# DI_DO.net
KiCad netlist of a schematic drawn in Altium Designer
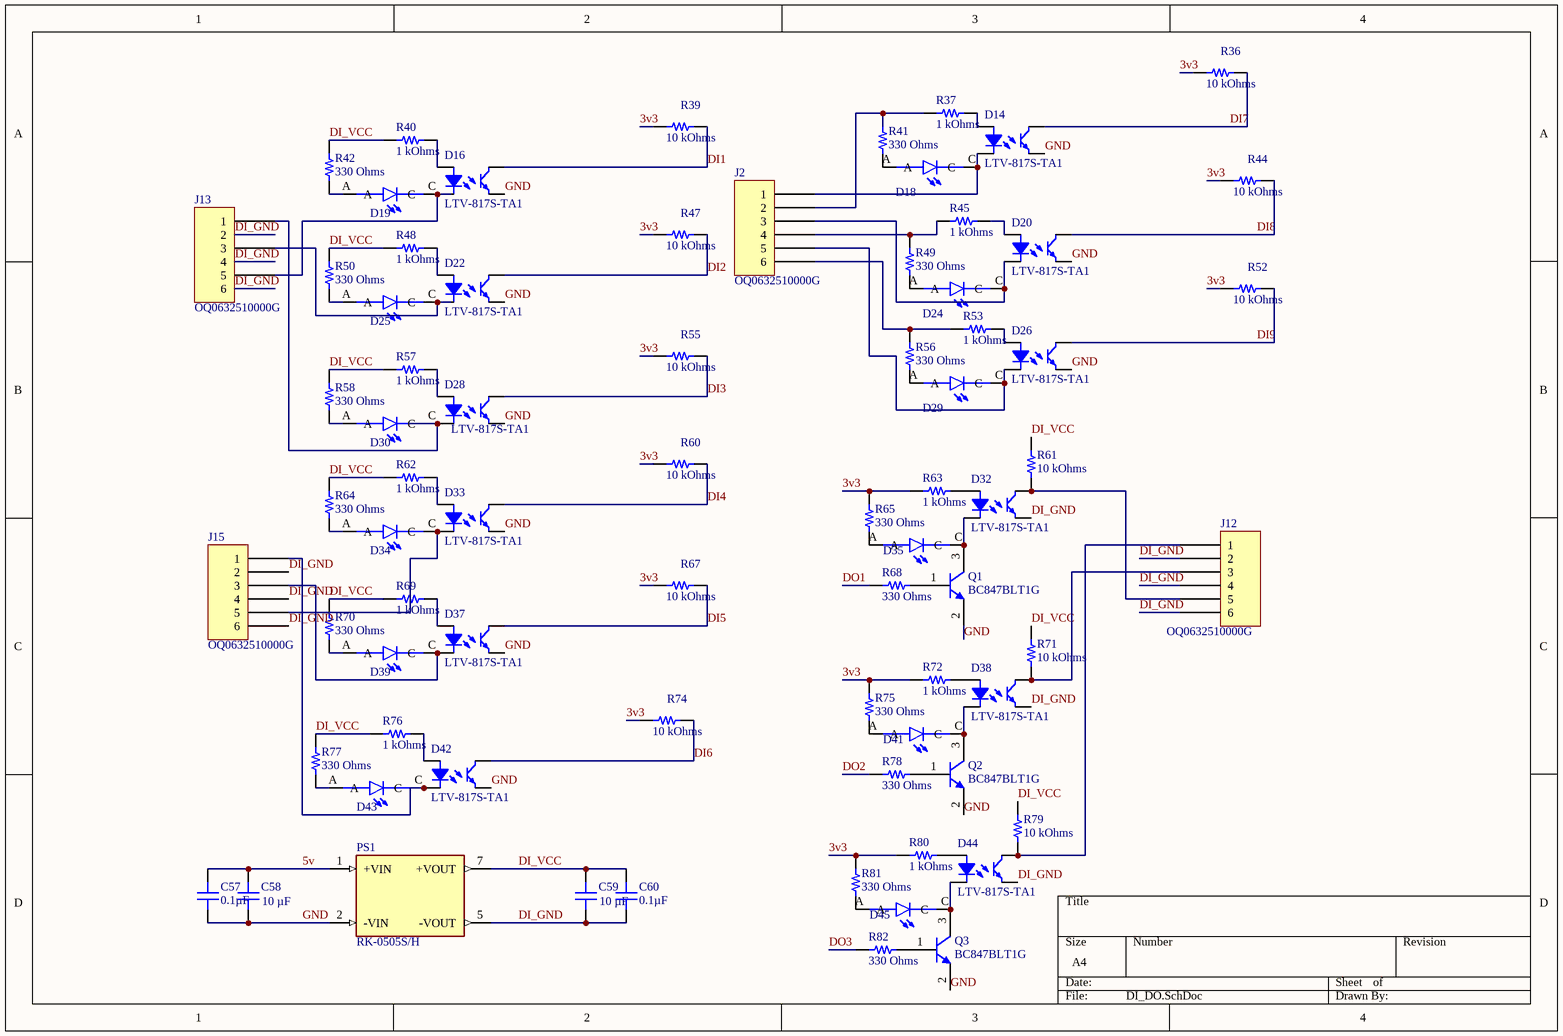
[diagram p0: DI_DO.SchDoc]

(export (version "E")
  (design (tool "Eeschema 10.0.6"))
  (components
    (comp (ref "C57")
      (value "1µF")
      (footprint "CAP 0805_2012")
      (description "CAP CER 1UF 10V X7R 0805")
      (fields
        (field (name "PART NUMBER") "0805ZC105KAT4A")
        (field (name "CAPACITANCE") "0.1µF")
        (field (name "MANUFACTURER") "AVX Corporation")
      )
      (libsource (lib "Celestial Altium Library - altium_library") (part "Capacitor"))
    )
    (comp (ref "C58")
      (value "10 µF")
      (footprint "CAP 1206_3216 - 0.8MM")
      (description "CAP CER 10UF 16V X5R 1206")
      (fields
        (field (name "PART NUMBER") "EMK316BJ106MD-T")
        (field (name "CAPACITANCE") "10 µF")
        (field (name "MANUFACTURER") "Taiyo Yuden")
      )
      (libsource (lib "Celestial Altium Library - altium_library") (part "Capacitor"))
    )
    (comp (ref "C59")
      (value "10 µF")
      (footprint "CAP 1206_3216 - 0.8MM")
      (description "CAP CER 10UF 16V X5R 1206")
      (fields
        (field (name "PART NUMBER") "EMK316BJ106MD-T")
        (field (name "CAPACITANCE") "10 µF")
        (field (name "MANUFACTURER") "Taiyo Yuden")
      )
      (libsource (lib "Celestial Altium Library - altium_library") (part "Capacitor"))
    )
    (comp (ref "C60")
      (value "1µF")
      (footprint "CAP 0805_2012")
      (description "CAP CER 1UF 10V X7R 0805")
      (fields
        (field (name "PART NUMBER") "0805ZC105KAT4A")
        (field (name "CAPACITANCE") "0.1µF")
        (field (name "MANUFACTURER") "AVX Corporation")
      )
      (libsource (lib "Celestial Altium Library - altium_library") (part "Capacitor"))
    )
    (comp (ref "D14")
      (value "LTV-817S-TA1")
      (footprint "LITEON LTV-817")
      (description "OPTOISOLATR 5KV TRANSISTOR 4-SMD")
      (fields (field (name "MANUFACTURER") "Lite-On Inc."))
      (libsource (lib "Celestial Altium Library - altium_library") (part "Optoisolator"))
    )
    (comp (ref "D16")
      (value "LTV-817S-TA1")
      (footprint "LITEON LTV-817")
      (description "OPTOISOLATR 5KV TRANSISTOR 4-SMD")
      (fields (field (name "MANUFACTURER") "Lite-On Inc."))
      (libsource (lib "Celestial Altium Library - altium_library") (part "Optoisolator"))
    )
    (comp (ref "D18")
      (value "597-3305-607F")
      (footprint "LEDC2012X70N")
      (description "LED Uni-Color Green 4-Pin Chip 0805 T/R")
      (libsource (lib "597-3305-607F") (part "597-3305-607F"))
    )
    (comp (ref "D19")
      (value "597-3305-607F")
      (footprint "LEDC2012X70N")
      (description "LED Uni-Color Green 4-Pin Chip 0805 T/R")
      (libsource (lib "597-3305-607F") (part "597-3305-607F"))
    )
    (comp (ref "D20")
      (value "LTV-817S-TA1")
      (footprint "LITEON LTV-817")
      (description "OPTOISOLATR 5KV TRANSISTOR 4-SMD")
      (fields (field (name "MANUFACTURER") "Lite-On Inc."))
      (libsource (lib "Celestial Altium Library - altium_library") (part "Optoisolator"))
    )
    (comp (ref "D22")
      (value "LTV-817S-TA1")
      (footprint "LITEON LTV-817")
      (description "OPTOISOLATR 5KV TRANSISTOR 4-SMD")
      (fields (field (name "MANUFACTURER") "Lite-On Inc."))
      (libsource (lib "Celestial Altium Library - altium_library") (part "Optoisolator"))
    )
    (comp (ref "D24")
      (value "597-3305-607F")
      (footprint "LEDC2012X70N")
      (description "LED Uni-Color Green 4-Pin Chip 0805 T/R")
      (libsource (lib "597-3305-607F") (part "597-3305-607F"))
    )
    (comp (ref "D25")
      (value "597-3305-607F")
      (footprint "LEDC2012X70N")
      (description "LED Uni-Color Green 4-Pin Chip 0805 T/R")
      (libsource (lib "597-3305-607F") (part "597-3305-607F"))
    )
    (comp (ref "D26")
      (value "LTV-817S-TA1")
      (footprint "LITEON LTV-817")
      (description "OPTOISOLATR 5KV TRANSISTOR 4-SMD")
      (fields (field (name "MANUFACTURER") "Lite-On Inc."))
      (libsource (lib "Celestial Altium Library - altium_library") (part "Optoisolator"))
    )
    (comp (ref "D28")
      (value "LTV-817S-TA1")
      (footprint "LITEON LTV-817")
      (description "OPTOISOLATR 5KV TRANSISTOR 4-SMD")
      (fields (field (name "MANUFACTURER") "Lite-On Inc."))
      (libsource (lib "Celestial Altium Library - altium_library") (part "Optoisolator"))
    )
    (comp (ref "D29")
      (value "597-3305-607F")
      (footprint "LEDC2012X70N")
      (description "LED Uni-Color Green 4-Pin Chip 0805 T/R")
      (libsource (lib "597-3305-607F") (part "597-3305-607F"))
    )
    (comp (ref "D30")
      (value "597-3305-607F")
      (footprint "LEDC2012X70N")
      (description "LED Uni-Color Green 4-Pin Chip 0805 T/R")
      (libsource (lib "597-3305-607F") (part "597-3305-607F"))
    )
    (comp (ref "D32")
      (value "LTV-817S-TA1")
      (footprint "LITEON LTV-817")
      (description "OPTOISOLATR 5KV TRANSISTOR 4-SMD")
      (fields (field (name "MANUFACTURER") "Lite-On Inc."))
      (libsource (lib "Celestial Altium Library - altium_library") (part "Optoisolator"))
    )
    (comp (ref "D33")
      (value "LTV-817S-TA1")
      (footprint "LITEON LTV-817")
      (description "OPTOISOLATR 5KV TRANSISTOR 4-SMD")
      (fields (field (name "MANUFACTURER") "Lite-On Inc."))
      (libsource (lib "Celestial Altium Library - altium_library") (part "Optoisolator"))
    )
    (comp (ref "D34")
      (value "597-3305-607F")
      (footprint "LEDC2012X70N")
      (description "LED Uni-Color Green 4-Pin Chip 0805 T/R")
      (libsource (lib "597-3305-607F") (part "597-3305-607F"))
    )
    (comp (ref "D35")
      (value "597-3305-607F")
      (footprint "LEDC2012X70N")
      (description "LED Uni-Color Green 4-Pin Chip 0805 T/R")
      (libsource (lib "597-3305-607F") (part "597-3305-607F"))
    )
    (comp (ref "D37")
      (value "LTV-817S-TA1")
      (footprint "LITEON LTV-817")
      (description "OPTOISOLATR 5KV TRANSISTOR 4-SMD")
      (fields (field (name "MANUFACTURER") "Lite-On Inc."))
      (libsource (lib "Celestial Altium Library - altium_library") (part "Optoisolator"))
    )
    (comp (ref "D38")
      (value "LTV-817S-TA1")
      (footprint "LITEON LTV-817")
      (description "OPTOISOLATR 5KV TRANSISTOR 4-SMD")
      (fields (field (name "MANUFACTURER") "Lite-On Inc."))
      (libsource (lib "Celestial Altium Library - altium_library") (part "Optoisolator"))
    )
    (comp (ref "D39")
      (value "597-3305-607F")
      (footprint "LEDC2012X70N")
      (description "LED Uni-Color Green 4-Pin Chip 0805 T/R")
      (libsource (lib "597-3305-607F") (part "597-3305-607F"))
    )
    (comp (ref "D41")
      (value "597-3305-607F")
      (footprint "LEDC2012X70N")
      (description "LED Uni-Color Green 4-Pin Chip 0805 T/R")
      (libsource (lib "597-3305-607F") (part "597-3305-607F"))
    )
    (comp (ref "D42")
      (value "LTV-817S-TA1")
      (footprint "LITEON LTV-817")
      (description "OPTOISOLATR 5KV TRANSISTOR 4-SMD")
      (fields (field (name "MANUFACTURER") "Lite-On Inc."))
      (libsource (lib "Celestial Altium Library - altium_library") (part "Optoisolator"))
    )
    (comp (ref "D43")
      (value "597-3305-607F")
      (footprint "LEDC2012X70N")
      (description "LED Uni-Color Green 4-Pin Chip 0805 T/R")
      (libsource (lib "597-3305-607F") (part "597-3305-607F"))
    )
    (comp (ref "D44")
      (value "LTV-817S-TA1")
      (footprint "LITEON LTV-817")
      (description "OPTOISOLATR 5KV TRANSISTOR 4-SMD")
      (fields (field (name "MANUFACTURER") "Lite-On Inc."))
      (libsource (lib "Celestial Altium Library - altium_library") (part "Optoisolator"))
    )
    (comp (ref "D45")
      (value "597-3305-607F")
      (footprint "LEDC2012X70N")
      (description "LED Uni-Color Green 4-Pin Chip 0805 T/R")
      (libsource (lib "597-3305-607F") (part "597-3305-607F"))
    )
    (comp (ref "J2")
      (value "OQ0632510000G")
      (footprint "FCI 06-381-6PIN")
      (description "TERM BLOCK HDR 6POS 90DEG 3.81MM")
      (fields (field (name "MANUFACTURER") "Amphenol Anytek"))
      (libsource (lib "Celestial Altium Library - altium_library") (part "6 Pin"))
    )
    (comp (ref "J12")
      (value "OQ0632510000G")
      (footprint "FCI 06-381-6PIN")
      (description "TERM BLOCK HDR 6POS 90DEG 3.81MM")
      (fields (field (name "MANUFACTURER") "Amphenol Anytek"))
      (libsource (lib "") (part "6 Pin_1"))
    )
    (comp (ref "J13")
      (value "OQ0632510000G")
      (footprint "FCI 06-381-6PIN")
      (description "TERM BLOCK HDR 6POS 90DEG 3.81MM")
      (fields (field (name "MANUFACTURER") "Amphenol Anytek"))
      (libsource (lib "Celestial Altium Library - altium_library") (part "6 Pin"))
    )
    (comp (ref "J15")
      (value "OQ0632510000G")
      (footprint "FCI 06-381-6PIN")
      (description "TERM BLOCK HDR 6POS 90DEG 3.81MM")
      (fields (field (name "MANUFACTURER") "Amphenol Anytek"))
      (libsource (lib "Celestial Altium Library - altium_library") (part "6 Pin"))
    )
    (comp (ref "PS1")
      (value "RK-0505S/H")
      (footprint "CONV_RK-0505S/H")
      (description "DC/DC Converter, 1 Watt, SIP7, Single Output")
      (fields (field (name "MF") "{'manufacturer': u'Recom Power'}"))
      (libsource (lib "RK-0505S_H") (part "RK-0505S/H"))
    )
    (comp (ref "Q1")
      (value "BC847BLT1G")
      (footprint "ON SEMI SOT-23-3")
      (description "TRANS NPN 45V 0.1A SOT23")
      (fields (field (name "MANUFACTURER") "ON Semiconductor"))
      (libsource (lib "Celestial Altium Library - altium_library") (part "ON SEMI NPN SOT-23-3"))
    )
    (comp (ref "Q2")
      (value "BC847BLT1G")
      (footprint "ON SEMI SOT-23-3")
      (description "TRANS NPN 45V 0.1A SOT23")
      (fields (field (name "MANUFACTURER") "ON Semiconductor"))
      (libsource (lib "Celestial Altium Library - altium_library") (part "ON SEMI NPN SOT-23-3"))
    )
    (comp (ref "Q3")
      (value "BC847BLT1G")
      (footprint "ON SEMI SOT-23-3")
      (description "TRANS NPN 45V 0.1A SOT23")
      (fields (field (name "MANUFACTURER") "ON Semiconductor"))
      (libsource (lib "Celestial Altium Library - altium_library") (part "ON SEMI NPN SOT-23-3"))
    )
    (comp (ref "R36")
      (value "10 kOhms")
      (footprint "RES 0805_2012")
      (description "RES SMD 10K OHM 1% 0.4W 0805")
      (fields (field (name "PART NUMBER") "ESR10EZPF1002") (field (name "MANUFACTURER") "Rohm Semiconductor"))
      (libsource (lib "Celestial Altium Library - altium_library") (part "Resistor"))
    )
    (comp (ref "R37")
      (value "1 kOhms")
      (footprint "RES 0805_2012")
      (description "RES SMD 1K OHM 1% 0.4W 0805")
      (fields (field (name "PART NUMBER") "ESR10EZPF1001") (field (name "MANUFACTURER") "Rohm Semiconductor"))
      (libsource (lib "Celestial Altium Library - altium_library") (part "Resistor"))
    )
    (comp (ref "R39")
      (value "10 kOhms")
      (footprint "RES 0805_2012")
      (description "RES SMD 10K OHM 1% 0.4W 0805")
      (fields (field (name "PART NUMBER") "ESR10EZPF1002") (field (name "MANUFACTURER") "Rohm Semiconductor"))
      (libsource (lib "Celestial Altium Library - altium_library") (part "Resistor"))
    )
    (comp (ref "R40")
      (value "1 kOhms")
      (footprint "RES 0805_2012")
      (description "RES SMD 1K OHM 1% 0.4W 0805")
      (fields (field (name "PART NUMBER") "ESR10EZPF1001") (field (name "MANUFACTURER") "Rohm Semiconductor"))
      (libsource (lib "Celestial Altium Library - altium_library") (part "Resistor"))
    )
    (comp (ref "R41")
      (value "330 Ohms")
      (footprint "RES 0805_2012")
      (description "RES SMD 330 OHM 1% 1/2W 0805")
      (fields (field (name "PART NUMBER") "CRCW0805330RFKEAHP") (field (name "MANUFACTURER") "Vishay Dale"))
      (libsource (lib "Celestial Altium Library - altium_library") (part "Resistor"))
    )
    (comp (ref "R42")
      (value "330 Ohms")
      (footprint "RES 0805_2012")
      (description "RES SMD 330 OHM 1% 1/2W 0805")
      (fields (field (name "PART NUMBER") "CRCW0805330RFKEAHP") (field (name "MANUFACTURER") "Vishay Dale"))
      (libsource (lib "Celestial Altium Library - altium_library") (part "Resistor"))
    )
    (comp (ref "R44")
      (value "10 kOhms")
      (footprint "RES 0805_2012")
      (description "RES SMD 10K OHM 1% 0.4W 0805")
      (fields (field (name "PART NUMBER") "ESR10EZPF1002") (field (name "MANUFACTURER") "Rohm Semiconductor"))
      (libsource (lib "Celestial Altium Library - altium_library") (part "Resistor"))
    )
    (comp (ref "R45")
      (value "1 kOhms")
      (footprint "RES 0805_2012")
      (description "RES SMD 1K OHM 1% 0.4W 0805")
      (fields (field (name "PART NUMBER") "ESR10EZPF1001") (field (name "MANUFACTURER") "Rohm Semiconductor"))
      (libsource (lib "Celestial Altium Library - altium_library") (part "Resistor"))
    )
    (comp (ref "R47")
      (value "10 kOhms")
      (footprint "RES 0805_2012")
      (description "RES SMD 10K OHM 1% 0.4W 0805")
      (fields (field (name "PART NUMBER") "ESR10EZPF1002") (field (name "MANUFACTURER") "Rohm Semiconductor"))
      (libsource (lib "Celestial Altium Library - altium_library") (part "Resistor"))
    )
    (comp (ref "R48")
      (value "1 kOhms")
      (footprint "RES 0805_2012")
      (description "RES SMD 1K OHM 1% 0.4W 0805")
      (fields (field (name "PART NUMBER") "ESR10EZPF1001") (field (name "MANUFACTURER") "Rohm Semiconductor"))
      (libsource (lib "Celestial Altium Library - altium_library") (part "Resistor"))
    )
    (comp (ref "R49")
      (value "330 Ohms")
      (footprint "RES 0805_2012")
      (description "RES SMD 330 OHM 1% 1/2W 0805")
      (fields (field (name "PART NUMBER") "CRCW0805330RFKEAHP") (field (name "MANUFACTURER") "Vishay Dale"))
      (libsource (lib "Celestial Altium Library - altium_library") (part "Resistor"))
    )
    (comp (ref "R50")
      (value "330 Ohms")
      (footprint "RES 0805_2012")
      (description "RES SMD 330 OHM 1% 1/2W 0805")
      (fields (field (name "PART NUMBER") "CRCW0805330RFKEAHP") (field (name "MANUFACTURER") "Vishay Dale"))
      (libsource (lib "Celestial Altium Library - altium_library") (part "Resistor"))
    )
    (comp (ref "R52")
      (value "10 kOhms")
      (footprint "RES 0805_2012")
      (description "RES SMD 10K OHM 1% 0.4W 0805")
      (fields (field (name "PART NUMBER") "ESR10EZPF1002") (field (name "MANUFACTURER") "Rohm Semiconductor"))
      (libsource (lib "Celestial Altium Library - altium_library") (part "Resistor"))
    )
    (comp (ref "R53")
      (value "1 kOhms")
      (footprint "RES 0805_2012")
      (description "RES SMD 1K OHM 1% 0.4W 0805")
      (fields (field (name "PART NUMBER") "ESR10EZPF1001") (field (name "MANUFACTURER") "Rohm Semiconductor"))
      (libsource (lib "Celestial Altium Library - altium_library") (part "Resistor"))
    )
    (comp (ref "R55")
      (value "10 kOhms")
      (footprint "RES 0805_2012")
      (description "RES SMD 10K OHM 1% 0.4W 0805")
      (fields (field (name "PART NUMBER") "ESR10EZPF1002") (field (name "MANUFACTURER") "Rohm Semiconductor"))
      (libsource (lib "Celestial Altium Library - altium_library") (part "Resistor"))
    )
    (comp (ref "R56")
      (value "330 Ohms")
      (footprint "RES 0805_2012")
      (description "RES SMD 330 OHM 1% 1/2W 0805")
      (fields (field (name "PART NUMBER") "CRCW0805330RFKEAHP") (field (name "MANUFACTURER") "Vishay Dale"))
      (libsource (lib "Celestial Altium Library - altium_library") (part "Resistor"))
    )
    (comp (ref "R57")
      (value "1 kOhms")
      (footprint "RES 0805_2012")
      (description "RES SMD 1K OHM 1% 0.4W 0805")
      (fields (field (name "PART NUMBER") "ESR10EZPF1001") (field (name "MANUFACTURER") "Rohm Semiconductor"))
      (libsource (lib "Celestial Altium Library - altium_library") (part "Resistor"))
    )
    (comp (ref "R58")
      (value "330 Ohms")
      (footprint "RES 0805_2012")
      (description "RES SMD 330 OHM 1% 1/2W 0805")
      (fields (field (name "PART NUMBER") "CRCW0805330RFKEAHP") (field (name "MANUFACTURER") "Vishay Dale"))
      (libsource (lib "Celestial Altium Library - altium_library") (part "Resistor"))
    )
    (comp (ref "R60")
      (value "10 kOhms")
      (footprint "RES 0805_2012")
      (description "RES SMD 10K OHM 1% 0.4W 0805")
      (fields (field (name "PART NUMBER") "ESR10EZPF1002") (field (name "MANUFACTURER") "Rohm Semiconductor"))
      (libsource (lib "Celestial Altium Library - altium_library") (part "Resistor"))
    )
    (comp (ref "R61")
      (value "10 kOhms")
      (footprint "RES 0805_2012")
      (description "RES SMD 10K OHM 1% 0.4W 0805")
      (fields (field (name "PART NUMBER") "ESR10EZPF1002") (field (name "MANUFACTURER") "Rohm Semiconductor"))
      (libsource (lib "Celestial Altium Library - altium_library") (part "Resistor"))
    )
    (comp (ref "R62")
      (value "1 kOhms")
      (footprint "RES 0805_2012")
      (description "RES SMD 1K OHM 1% 0.4W 0805")
      (fields (field (name "PART NUMBER") "ESR10EZPF1001") (field (name "MANUFACTURER") "Rohm Semiconductor"))
      (libsource (lib "Celestial Altium Library - altium_library") (part "Resistor"))
    )
    (comp (ref "R63")
      (value "1 kOhms")
      (footprint "RES 0805_2012")
      (description "RES SMD 1K OHM 1% 0.4W 0805")
      (fields (field (name "PART NUMBER") "ESR10EZPF1001") (field (name "MANUFACTURER") "Rohm Semiconductor"))
      (libsource (lib "Celestial Altium Library - altium_library") (part "Resistor"))
    )
    (comp (ref "R64")
      (value "330 Ohms")
      (footprint "RES 0805_2012")
      (description "RES SMD 330 OHM 1% 1/2W 0805")
      (fields (field (name "PART NUMBER") "CRCW0805330RFKEAHP") (field (name "MANUFACTURER") "Vishay Dale"))
      (libsource (lib "Celestial Altium Library - altium_library") (part "Resistor"))
    )
    (comp (ref "R65")
      (value "330 Ohms")
      (footprint "RES 0805_2012")
      (description "RES SMD 330 OHM 1% 1/2W 0805")
      (fields (field (name "PART NUMBER") "CRCW0805330RFKEAHP") (field (name "MANUFACTURER") "Vishay Dale"))
      (libsource (lib "Celestial Altium Library - altium_library") (part "Resistor"))
    )
    (comp (ref "R67")
      (value "10 kOhms")
      (footprint "RES 0805_2012")
      (description "RES SMD 10K OHM 1% 0.4W 0805")
      (fields (field (name "PART NUMBER") "ESR10EZPF1002") (field (name "MANUFACTURER") "Rohm Semiconductor"))
      (libsource (lib "Celestial Altium Library - altium_library") (part "Resistor"))
    )
    (comp (ref "R68")
      (value "330 Ohms")
      (footprint "RES 0805_2012")
      (description "RES SMD 330 OHM 1% 1/2W 0805")
      (fields (field (name "PART NUMBER") "CRCW0805330RFKEAHP") (field (name "MANUFACTURER") "Vishay Dale"))
      (libsource (lib "Celestial Altium Library - altium_library") (part "Resistor"))
    )
    (comp (ref "R69")
      (value "1 kOhms")
      (footprint "RES 0805_2012")
      (description "RES SMD 1K OHM 1% 0.4W 0805")
      (fields (field (name "PART NUMBER") "ESR10EZPF1001") (field (name "MANUFACTURER") "Rohm Semiconductor"))
      (libsource (lib "Celestial Altium Library - altium_library") (part "Resistor"))
    )
    (comp (ref "R70")
      (value "330 Ohms")
      (footprint "RES 0805_2012")
      (description "RES SMD 330 OHM 1% 1/2W 0805")
      (fields (field (name "PART NUMBER") "CRCW0805330RFKEAHP") (field (name "MANUFACTURER") "Vishay Dale"))
      (libsource (lib "Celestial Altium Library - altium_library") (part "Resistor"))
    )
    (comp (ref "R71")
      (value "10 kOhms")
      (footprint "RES 0805_2012")
      (description "RES SMD 10K OHM 1% 0.4W 0805")
      (fields (field (name "PART NUMBER") "ESR10EZPF1002") (field (name "MANUFACTURER") "Rohm Semiconductor"))
      (libsource (lib "Celestial Altium Library - altium_library") (part "Resistor"))
    )
    (comp (ref "R72")
      (value "1 kOhms")
      (footprint "RES 0805_2012")
      (description "RES SMD 1K OHM 1% 0.4W 0805")
      (fields (field (name "PART NUMBER") "ESR10EZPF1001") (field (name "MANUFACTURER") "Rohm Semiconductor"))
      (libsource (lib "Celestial Altium Library - altium_library") (part "Resistor"))
    )
    (comp (ref "R74")
      (value "10 kOhms")
      (footprint "RES 0805_2012")
      (description "RES SMD 10K OHM 1% 0.4W 0805")
      (fields (field (name "PART NUMBER") "ESR10EZPF1002") (field (name "MANUFACTURER") "Rohm Semiconductor"))
      (libsource (lib "Celestial Altium Library - altium_library") (part "Resistor"))
    )
    (comp (ref "R75")
      (value "330 Ohms")
      (footprint "RES 0805_2012")
      (description "RES SMD 330 OHM 1% 1/2W 0805")
      (fields (field (name "PART NUMBER") "CRCW0805330RFKEAHP") (field (name "MANUFACTURER") "Vishay Dale"))
      (libsource (lib "Celestial Altium Library - altium_library") (part "Resistor"))
    )
    (comp (ref "R76")
      (value "1 kOhms")
      (footprint "RES 0805_2012")
      (description "RES SMD 1K OHM 1% 0.4W 0805")
      (fields (field (name "PART NUMBER") "ESR10EZPF1001") (field (name "MANUFACTURER") "Rohm Semiconductor"))
      (libsource (lib "Celestial Altium Library - altium_library") (part "Resistor"))
    )
    (comp (ref "R77")
      (value "330 Ohms")
      (footprint "RES 0805_2012")
      (description "RES SMD 330 OHM 1% 1/2W 0805")
      (fields (field (name "PART NUMBER") "CRCW0805330RFKEAHP") (field (name "MANUFACTURER") "Vishay Dale"))
      (libsource (lib "Celestial Altium Library - altium_library") (part "Resistor"))
    )
    (comp (ref "R78")
      (value "330 Ohms")
      (footprint "RES 0805_2012")
      (description "RES SMD 330 OHM 1% 1/2W 0805")
      (fields (field (name "PART NUMBER") "CRCW0805330RFKEAHP") (field (name "MANUFACTURER") "Vishay Dale"))
      (libsource (lib "Celestial Altium Library - altium_library") (part "Resistor"))
    )
    (comp (ref "R79")
      (value "10 kOhms")
      (footprint "RES 0805_2012")
      (description "RES SMD 10K OHM 1% 0.4W 0805")
      (fields (field (name "PART NUMBER") "ESR10EZPF1002") (field (name "MANUFACTURER") "Rohm Semiconductor"))
      (libsource (lib "Celestial Altium Library - altium_library") (part "Resistor"))
    )
    (comp (ref "R80")
      (value "1 kOhms")
      (footprint "RES 0805_2012")
      (description "RES SMD 1K OHM 1% 0.4W 0805")
      (fields (field (name "PART NUMBER") "ESR10EZPF1001") (field (name "MANUFACTURER") "Rohm Semiconductor"))
      (libsource (lib "Celestial Altium Library - altium_library") (part "Resistor"))
    )
    (comp (ref "R81")
      (value "330 Ohms")
      (footprint "RES 0805_2012")
      (description "RES SMD 330 OHM 1% 1/2W 0805")
      (fields (field (name "PART NUMBER") "CRCW0805330RFKEAHP") (field (name "MANUFACTURER") "Vishay Dale"))
      (libsource (lib "Celestial Altium Library - altium_library") (part "Resistor"))
    )
    (comp (ref "R82")
      (value "330 Ohms")
      (footprint "RES 0805_2012")
      (description "RES SMD 330 OHM 1% 1/2W 0805")
      (fields (field (name "PART NUMBER") "CRCW0805330RFKEAHP") (field (name "MANUFACTURER") "Vishay Dale"))
      (libsource (lib "Celestial Altium Library - altium_library") (part "Resistor"))
    )
  )
  (nets
    (net (code "1") (name "/3v3") (class "Default")
      (node (ref "R36") (pin "2") (pinfunction "2_2") (pintype "passive"))
      (node (ref "R39") (pin "2") (pinfunction "2_2") (pintype "passive"))
      (node (ref "R44") (pin "2") (pinfunction "2_2") (pintype "passive"))
      (node (ref "R47") (pin "2") (pinfunction "2_2") (pintype "passive"))
      (node (ref "R52") (pin "2") (pinfunction "2_2") (pintype "passive"))
      (node (ref "R55") (pin "2") (pinfunction "2_2") (pintype "passive"))
      (node (ref "R60") (pin "2") (pinfunction "2_2") (pintype "passive"))
      (node (ref "R63") (pin "1") (pinfunction "1_1") (pintype "passive"))
      (node (ref "R65") (pin "1") (pinfunction "1_1") (pintype "passive"))
      (node (ref "R67") (pin "2") (pinfunction "2_2") (pintype "passive"))
      (node (ref "R72") (pin "1") (pinfunction "1_1") (pintype "passive"))
      (node (ref "R74") (pin "2") (pinfunction "2_2") (pintype "passive"))
      (node (ref "R75") (pin "1") (pinfunction "1_1") (pintype "passive"))
      (node (ref "R80") (pin "1") (pinfunction "1_1") (pintype "passive"))
      (node (ref "R81") (pin "1") (pinfunction "1_1") (pintype "passive"))
    )
    (net (code "2") (name "/5v") (class "Default")
      (node (ref "C57") (pin "2") (pinfunction "2_2") (pintype "passive"))
      (node (ref "C58") (pin "2") (pinfunction "2_2") (pintype "passive"))
      (node (ref "PS1") (pin "1") (pinfunction "+VIN_1") (pintype "input"))
    )
    (net (code "3") (name "/DI1") (class "Default")
      (node (ref "D16") (pin "4") (pinfunction "4_4") (pintype "passive"))
      (node (ref "R39") (pin "1") (pinfunction "1_1") (pintype "passive"))
    )
    (net (code "4") (name "/DI2") (class "Default")
      (node (ref "D22") (pin "4") (pinfunction "4_4") (pintype "passive"))
      (node (ref "R47") (pin "1") (pinfunction "1_1") (pintype "passive"))
    )
    (net (code "5") (name "/DI3") (class "Default")
      (node (ref "D28") (pin "4") (pinfunction "4_4") (pintype "passive"))
      (node (ref "R55") (pin "1") (pinfunction "1_1") (pintype "passive"))
    )
    (net (code "6") (name "/DI4") (class "Default")
      (node (ref "D33") (pin "4") (pinfunction "4_4") (pintype "passive"))
      (node (ref "R60") (pin "1") (pinfunction "1_1") (pintype "passive"))
    )
    (net (code "7") (name "/DI5") (class "Default")
      (node (ref "D37") (pin "4") (pinfunction "4_4") (pintype "passive"))
      (node (ref "R67") (pin "1") (pinfunction "1_1") (pintype "passive"))
    )
    (net (code "8") (name "/DI6") (class "Default")
      (node (ref "D42") (pin "4") (pinfunction "4_4") (pintype "passive"))
      (node (ref "R74") (pin "1") (pinfunction "1_1") (pintype "passive"))
    )
    (net (code "9") (name "/DI7") (class "Default")
      (node (ref "D14") (pin "4") (pinfunction "4_4") (pintype "passive"))
      (node (ref "R36") (pin "1") (pinfunction "1_1") (pintype "passive"))
    )
    (net (code "10") (name "/DI8") (class "Default")
      (node (ref "D20") (pin "4") (pinfunction "4_4") (pintype "passive"))
      (node (ref "R44") (pin "1") (pinfunction "1_1") (pintype "passive"))
    )
    (net (code "11") (name "/DI9") (class "Default")
      (node (ref "D26") (pin "4") (pinfunction "4_4") (pintype "passive"))
      (node (ref "R52") (pin "1") (pinfunction "1_1") (pintype "passive"))
    )
    (net (code "12") (name "/DI_GND") (class "Default")
      (node (ref "C59") (pin "1") (pinfunction "1_1") (pintype "passive"))
      (node (ref "C60") (pin "1") (pinfunction "1_1") (pintype "passive"))
      (node (ref "D32") (pin "3") (pinfunction "3_3") (pintype "passive"))
      (node (ref "D38") (pin "3") (pinfunction "3_3") (pintype "passive"))
      (node (ref "D44") (pin "3") (pinfunction "3_3") (pintype "passive"))
      (node (ref "J12") (pin "2") (pinfunction "2_2") (pintype "passive"))
      (node (ref "J12") (pin "4") (pinfunction "4_4") (pintype "passive"))
      (node (ref "J12") (pin "6") (pinfunction "6_6") (pintype "passive"))
      (node (ref "J13") (pin "2") (pinfunction "2_2") (pintype "passive"))
      (node (ref "J13") (pin "4") (pinfunction "4_4") (pintype "passive"))
      (node (ref "J13") (pin "6") (pinfunction "6_6") (pintype "passive"))
      (node (ref "J15") (pin "2") (pinfunction "2_2") (pintype "passive"))
      (node (ref "J15") (pin "4") (pinfunction "4_4") (pintype "passive"))
      (node (ref "J15") (pin "6") (pinfunction "6_6") (pintype "passive"))
      (node (ref "PS1") (pin "5") (pinfunction "-VOUT_5") (pintype "output"))
    )
    (net (code "13") (name "/DI_VCC") (class "Default")
      (node (ref "C59") (pin "2") (pinfunction "2_2") (pintype "passive"))
      (node (ref "C60") (pin "2") (pinfunction "2_2") (pintype "passive"))
      (node (ref "PS1") (pin "7") (pinfunction "+VOUT_7") (pintype "output"))
      (node (ref "R40") (pin "1") (pinfunction "1_1") (pintype "passive"))
      (node (ref "R42") (pin "2") (pinfunction "2_2") (pintype "passive"))
      (node (ref "R48") (pin "1") (pinfunction "1_1") (pintype "passive"))
      (node (ref "R50") (pin "2") (pinfunction "2_2") (pintype "passive"))
      (node (ref "R57") (pin "1") (pinfunction "1_1") (pintype "passive"))
      (node (ref "R58") (pin "2") (pinfunction "2_2") (pintype "passive"))
      (node (ref "R61") (pin "1") (pinfunction "1_1") (pintype "passive"))
      (node (ref "R62") (pin "1") (pinfunction "1_1") (pintype "passive"))
      (node (ref "R64") (pin "2") (pinfunction "2_2") (pintype "passive"))
      (node (ref "R69") (pin "1") (pinfunction "1_1") (pintype "passive"))
      (node (ref "R70") (pin "2") (pinfunction "2_2") (pintype "passive"))
      (node (ref "R71") (pin "1") (pinfunction "1_1") (pintype "passive"))
      (node (ref "R76") (pin "1") (pinfunction "1_1") (pintype "passive"))
      (node (ref "R77") (pin "2") (pinfunction "2_2") (pintype "passive"))
      (node (ref "R79") (pin "1") (pinfunction "1_1") (pintype "passive"))
    )
    (net (code "14") (name "/DO1") (class "Default")
      (node (ref "R68") (pin "1") (pinfunction "1_1") (pintype "passive"))
    )
    (net (code "15") (name "/DO2") (class "Default")
      (node (ref "R78") (pin "1") (pinfunction "1_1") (pintype "passive"))
    )
    (net (code "16") (name "/DO3") (class "Default")
      (node (ref "R82") (pin "1") (pinfunction "1_1") (pintype "passive"))
    )
    (net (code "17") (name "/GND") (class "Default")
      (node (ref "C57") (pin "1") (pinfunction "1_1") (pintype "passive"))
      (node (ref "C58") (pin "1") (pinfunction "1_1") (pintype "passive"))
      (node (ref "D14") (pin "3") (pinfunction "3_3") (pintype "passive"))
      (node (ref "D16") (pin "3") (pinfunction "3_3") (pintype "passive"))
      (node (ref "D20") (pin "3") (pinfunction "3_3") (pintype "passive"))
      (node (ref "D22") (pin "3") (pinfunction "3_3") (pintype "passive"))
      (node (ref "D26") (pin "3") (pinfunction "3_3") (pintype "passive"))
      (node (ref "D28") (pin "3") (pinfunction "3_3") (pintype "passive"))
      (node (ref "D33") (pin "3") (pinfunction "3_3") (pintype "passive"))
      (node (ref "D37") (pin "3") (pinfunction "3_3") (pintype "passive"))
      (node (ref "D42") (pin "3") (pinfunction "3_3") (pintype "passive"))
      (node (ref "PS1") (pin "2") (pinfunction "-VIN_2") (pintype "input"))
      (node (ref "Q1") (pin "2") (pinfunction "E_2") (pintype "passive"))
      (node (ref "Q2") (pin "2") (pinfunction "E_2") (pintype "passive"))
      (node (ref "Q3") (pin "2") (pinfunction "E_2") (pintype "passive"))
    )
    (net (code "18") (name "Net-(D14-Pad1)") (class "Default")
      (node (ref "D14") (pin "1") (pinfunction "1_1") (pintype "passive"))
      (node (ref "R37") (pin "2") (pinfunction "2_2") (pintype "passive"))
    )
    (net (code "19") (name "Net-(D14-Pad2)") (class "Default")
      (node (ref "D14") (pin "2") (pinfunction "2_2") (pintype "passive"))
      (node (ref "D18") (pin "C") (pinfunction "C_C") (pintype "passive"))
      (node (ref "J2") (pin "1") (pinfunction "1_1") (pintype "passive"))
    )
    (net (code "20") (name "Net-(D16-Pad1)") (class "Default")
      (node (ref "D16") (pin "1") (pinfunction "1_1") (pintype "passive"))
      (node (ref "R40") (pin "2") (pinfunction "2_2") (pintype "passive"))
    )
    (net (code "21") (name "Net-(D16-Pad2)") (class "Default")
      (node (ref "D16") (pin "2") (pinfunction "2_2") (pintype "passive"))
      (node (ref "D19") (pin "C") (pinfunction "C_C") (pintype "passive"))
      (node (ref "J13") (pin "5") (pinfunction "5_5") (pintype "passive"))
    )
    (net (code "22") (name "Net-(D18-PadA)") (class "Default")
      (node (ref "D18") (pin "A") (pinfunction "A_A") (pintype "passive"))
      (node (ref "R41") (pin "2") (pinfunction "2_2") (pintype "passive"))
    )
    (net (code "23") (name "Net-(D19-PadA)") (class "Default")
      (node (ref "D19") (pin "A") (pinfunction "A_A") (pintype "passive"))
      (node (ref "R42") (pin "1") (pinfunction "1_1") (pintype "passive"))
    )
    (net (code "24") (name "Net-(D20-Pad1)") (class "Default")
      (node (ref "D20") (pin "1") (pinfunction "1_1") (pintype "passive"))
      (node (ref "R45") (pin "2") (pinfunction "2_2") (pintype "passive"))
    )
    (net (code "25") (name "Net-(D20-Pad2)") (class "Default")
      (node (ref "D20") (pin "2") (pinfunction "2_2") (pintype "passive"))
      (node (ref "D24") (pin "C") (pinfunction "C_C") (pintype "passive"))
      (node (ref "J2") (pin "3") (pinfunction "3_3") (pintype "passive"))
    )
    (net (code "26") (name "Net-(D22-Pad1)") (class "Default")
      (node (ref "D22") (pin "1") (pinfunction "1_1") (pintype "passive"))
      (node (ref "R48") (pin "2") (pinfunction "2_2") (pintype "passive"))
    )
    (net (code "27") (name "Net-(D22-Pad2)") (class "Default")
      (node (ref "D22") (pin "2") (pinfunction "2_2") (pintype "passive"))
      (node (ref "D25") (pin "C") (pinfunction "C_C") (pintype "passive"))
      (node (ref "J13") (pin "3") (pinfunction "3_3") (pintype "passive"))
    )
    (net (code "28") (name "Net-(D24-PadA)") (class "Default")
      (node (ref "D24") (pin "A") (pinfunction "A_A") (pintype "passive"))
      (node (ref "R49") (pin "2") (pinfunction "2_2") (pintype "passive"))
    )
    (net (code "29") (name "Net-(D25-PadA)") (class "Default")
      (node (ref "D25") (pin "A") (pinfunction "A_A") (pintype "passive"))
      (node (ref "R50") (pin "1") (pinfunction "1_1") (pintype "passive"))
    )
    (net (code "30") (name "Net-(D26-Pad1)") (class "Default")
      (node (ref "D26") (pin "1") (pinfunction "1_1") (pintype "passive"))
      (node (ref "R53") (pin "2") (pinfunction "2_2") (pintype "passive"))
    )
    (net (code "31") (name "Net-(D26-Pad2)") (class "Default")
      (node (ref "D26") (pin "2") (pinfunction "2_2") (pintype "passive"))
      (node (ref "D29") (pin "C") (pinfunction "C_C") (pintype "passive"))
      (node (ref "J2") (pin "5") (pinfunction "5_5") (pintype "passive"))
    )
    (net (code "32") (name "Net-(D28-Pad1)") (class "Default")
      (node (ref "D28") (pin "1") (pinfunction "1_1") (pintype "passive"))
      (node (ref "R57") (pin "2") (pinfunction "2_2") (pintype "passive"))
    )
    (net (code "33") (name "Net-(D28-Pad2)") (class "Default")
      (node (ref "D28") (pin "2") (pinfunction "2_2") (pintype "passive"))
      (node (ref "D30") (pin "C") (pinfunction "C_C") (pintype "passive"))
      (node (ref "J13") (pin "1") (pinfunction "1_1") (pintype "passive"))
    )
    (net (code "34") (name "Net-(D29-PadA)") (class "Default")
      (node (ref "D29") (pin "A") (pinfunction "A_A") (pintype "passive"))
      (node (ref "R56") (pin "2") (pinfunction "2_2") (pintype "passive"))
    )
    (net (code "35") (name "Net-(D30-PadA)") (class "Default")
      (node (ref "D30") (pin "A") (pinfunction "A_A") (pintype "passive"))
      (node (ref "R58") (pin "1") (pinfunction "1_1") (pintype "passive"))
    )
    (net (code "36") (name "Net-(D32-Pad1)") (class "Default")
      (node (ref "D32") (pin "1") (pinfunction "1_1") (pintype "passive"))
      (node (ref "R63") (pin "2") (pinfunction "2_2") (pintype "passive"))
    )
    (net (code "37") (name "Net-(D32-Pad4)") (class "Default")
      (node (ref "D32") (pin "4") (pinfunction "4_4") (pintype "passive"))
      (node (ref "J12") (pin "5") (pinfunction "5_5") (pintype "passive"))
      (node (ref "R61") (pin "2") (pinfunction "2_2") (pintype "passive"))
    )
    (net (code "38") (name "Net-(D33-Pad1)") (class "Default")
      (node (ref "D33") (pin "1") (pinfunction "1_1") (pintype "passive"))
      (node (ref "R62") (pin "2") (pinfunction "2_2") (pintype "passive"))
    )
    (net (code "39") (name "Net-(D33-Pad2)") (class "Default")
      (node (ref "D33") (pin "2") (pinfunction "2_2") (pintype "passive"))
      (node (ref "D34") (pin "C") (pinfunction "C_C") (pintype "passive"))
      (node (ref "J15") (pin "5") (pinfunction "5_5") (pintype "passive"))
    )
    (net (code "40") (name "Net-(D34-PadA)") (class "Default")
      (node (ref "D34") (pin "A") (pinfunction "A_A") (pintype "passive"))
      (node (ref "R64") (pin "1") (pinfunction "1_1") (pintype "passive"))
    )
    (net (code "41") (name "Net-(D35-PadA)") (class "Default")
      (node (ref "D35") (pin "A") (pinfunction "A_A") (pintype "passive"))
      (node (ref "R65") (pin "2") (pinfunction "2_2") (pintype "passive"))
    )
    (net (code "42") (name "Net-(D37-Pad1)") (class "Default")
      (node (ref "D37") (pin "1") (pinfunction "1_1") (pintype "passive"))
      (node (ref "R69") (pin "2") (pinfunction "2_2") (pintype "passive"))
    )
    (net (code "43") (name "Net-(D37-Pad2)") (class "Default")
      (node (ref "D37") (pin "2") (pinfunction "2_2") (pintype "passive"))
      (node (ref "D39") (pin "C") (pinfunction "C_C") (pintype "passive"))
      (node (ref "J15") (pin "3") (pinfunction "3_3") (pintype "passive"))
    )
    (net (code "44") (name "Net-(D38-Pad1)") (class "Default")
      (node (ref "D38") (pin "1") (pinfunction "1_1") (pintype "passive"))
      (node (ref "R72") (pin "2") (pinfunction "2_2") (pintype "passive"))
    )
    (net (code "45") (name "Net-(D38-Pad4)") (class "Default")
      (node (ref "D38") (pin "4") (pinfunction "4_4") (pintype "passive"))
      (node (ref "J12") (pin "3") (pinfunction "3_3") (pintype "passive"))
      (node (ref "R71") (pin "2") (pinfunction "2_2") (pintype "passive"))
    )
    (net (code "46") (name "Net-(D39-PadA)") (class "Default")
      (node (ref "D39") (pin "A") (pinfunction "A_A") (pintype "passive"))
      (node (ref "R70") (pin "1") (pinfunction "1_1") (pintype "passive"))
    )
    (net (code "47") (name "Net-(D41-PadA)") (class "Default")
      (node (ref "D41") (pin "A") (pinfunction "A_A") (pintype "passive"))
      (node (ref "R75") (pin "2") (pinfunction "2_2") (pintype "passive"))
    )
    (net (code "48") (name "Net-(D42-Pad1)") (class "Default")
      (node (ref "D42") (pin "1") (pinfunction "1_1") (pintype "passive"))
      (node (ref "R76") (pin "2") (pinfunction "2_2") (pintype "passive"))
    )
    (net (code "49") (name "Net-(D42-Pad2)") (class "Default")
      (node (ref "D42") (pin "2") (pinfunction "2_2") (pintype "passive"))
      (node (ref "D43") (pin "C") (pinfunction "C_C") (pintype "passive"))
      (node (ref "J15") (pin "1") (pinfunction "1_1") (pintype "passive"))
    )
    (net (code "50") (name "Net-(D43-PadA)") (class "Default")
      (node (ref "D43") (pin "A") (pinfunction "A_A") (pintype "passive"))
      (node (ref "R77") (pin "1") (pinfunction "1_1") (pintype "passive"))
    )
    (net (code "51") (name "Net-(D44-Pad1)") (class "Default")
      (node (ref "D44") (pin "1") (pinfunction "1_1") (pintype "passive"))
      (node (ref "R80") (pin "2") (pinfunction "2_2") (pintype "passive"))
    )
    (net (code "52") (name "Net-(D44-Pad4)") (class "Default")
      (node (ref "D44") (pin "4") (pinfunction "4_4") (pintype "passive"))
      (node (ref "J12") (pin "1") (pinfunction "1_1") (pintype "passive"))
      (node (ref "R79") (pin "2") (pinfunction "2_2") (pintype "passive"))
    )
    (net (code "53") (name "Net-(D45-PadA)") (class "Default")
      (node (ref "D45") (pin "A") (pinfunction "A_A") (pintype "passive"))
      (node (ref "R81") (pin "2") (pinfunction "2_2") (pintype "passive"))
    )
    (net (code "54") (name "Net-(J2-Pad2)") (class "Default")
      (node (ref "J2") (pin "2") (pinfunction "2_2") (pintype "passive"))
      (node (ref "R37") (pin "1") (pinfunction "1_1") (pintype "passive"))
      (node (ref "R41") (pin "1") (pinfunction "1_1") (pintype "passive"))
    )
    (net (code "55") (name "Net-(J2-Pad4)") (class "Default")
      (node (ref "J2") (pin "4") (pinfunction "4_4") (pintype "passive"))
      (node (ref "R45") (pin "1") (pinfunction "1_1") (pintype "passive"))
      (node (ref "R49") (pin "1") (pinfunction "1_1") (pintype "passive"))
    )
    (net (code "56") (name "Net-(J2-Pad6)") (class "Default")
      (node (ref "J2") (pin "6") (pinfunction "6_6") (pintype "passive"))
      (node (ref "R53") (pin "1") (pinfunction "1_1") (pintype "passive"))
      (node (ref "R56") (pin "1") (pinfunction "1_1") (pintype "passive"))
    )
    (net (code "57") (name "Net-(Q1-B)") (class "Default")
      (node (ref "Q1") (pin "1") (pinfunction "B_1") (pintype "passive"))
      (node (ref "R68") (pin "2") (pinfunction "2_2") (pintype "passive"))
    )
    (net (code "58") (name "Net-(Q1-C)") (class "Default")
      (node (ref "D32") (pin "2") (pinfunction "2_2") (pintype "passive"))
      (node (ref "D35") (pin "C") (pinfunction "C_C") (pintype "passive"))
      (node (ref "Q1") (pin "3") (pinfunction "C_3") (pintype "passive"))
    )
    (net (code "59") (name "Net-(Q2-B)") (class "Default")
      (node (ref "Q2") (pin "1") (pinfunction "B_1") (pintype "passive"))
      (node (ref "R78") (pin "2") (pinfunction "2_2") (pintype "passive"))
    )
    (net (code "60") (name "Net-(Q2-C)") (class "Default")
      (node (ref "D38") (pin "2") (pinfunction "2_2") (pintype "passive"))
      (node (ref "D41") (pin "C") (pinfunction "C_C") (pintype "passive"))
      (node (ref "Q2") (pin "3") (pinfunction "C_3") (pintype "passive"))
    )
    (net (code "61") (name "Net-(Q3-B)") (class "Default")
      (node (ref "Q3") (pin "1") (pinfunction "B_1") (pintype "passive"))
      (node (ref "R82") (pin "2") (pinfunction "2_2") (pintype "passive"))
    )
    (net (code "62") (name "Net-(Q3-C)") (class "Default")
      (node (ref "D44") (pin "2") (pinfunction "2_2") (pintype "passive"))
      (node (ref "D45") (pin "C") (pinfunction "C_C") (pintype "passive"))
      (node (ref "Q3") (pin "3") (pinfunction "C_3") (pintype "passive"))
    )
  )
)
